# Sense.net
KiCad netlist of a schematic drawn in Altium Designer
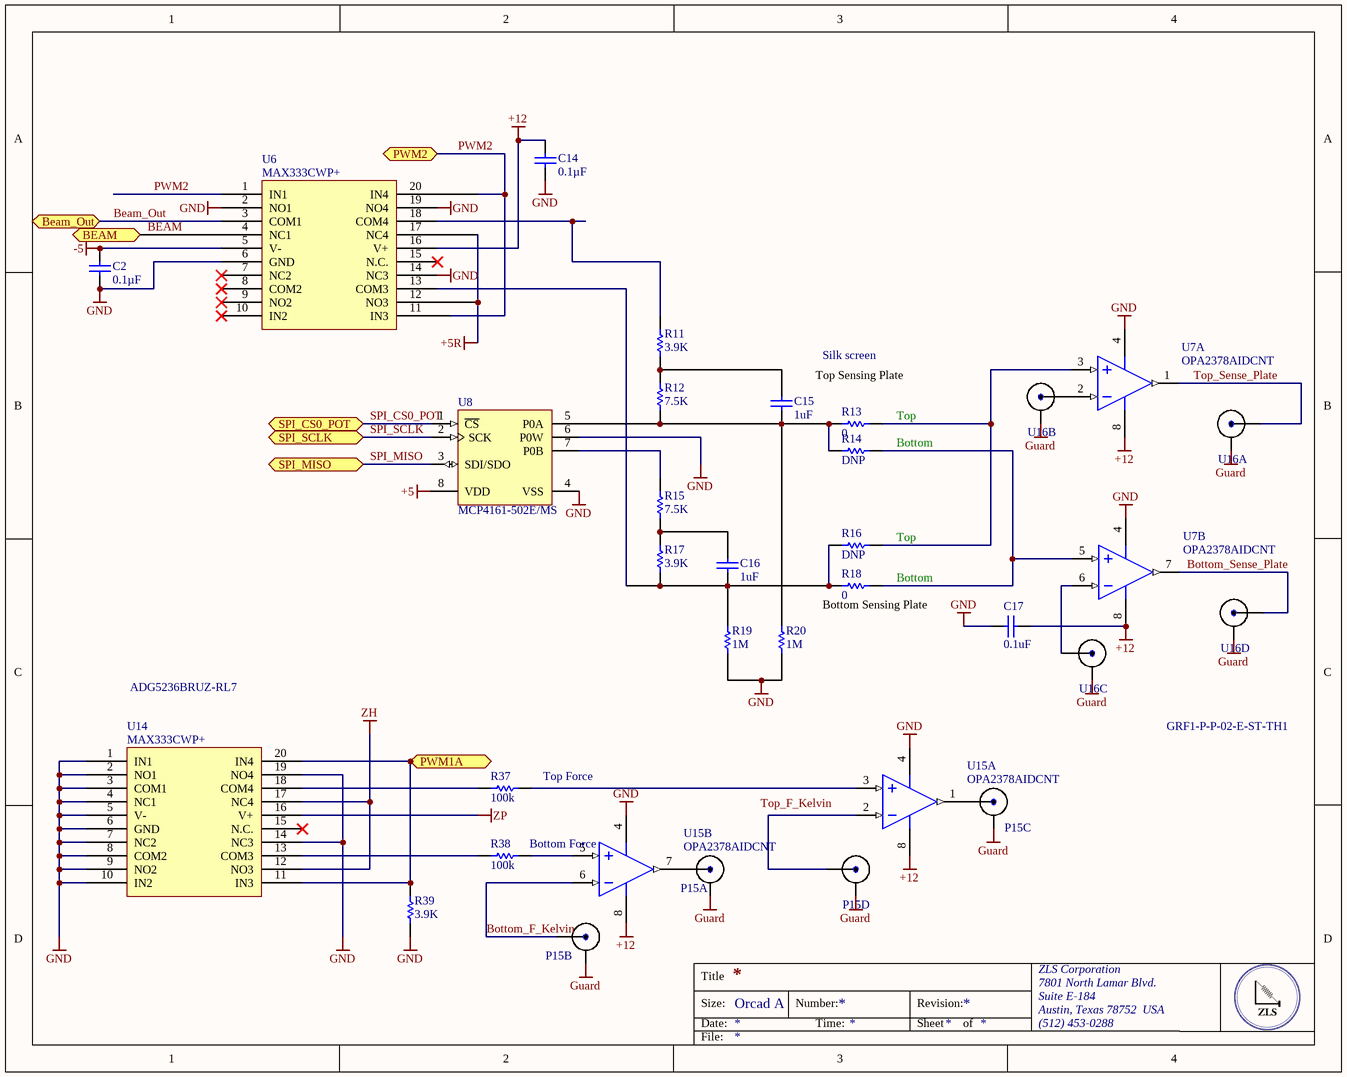
[diagram p0: Sense.SchDoc]

(export (version "E")
  (design (tool "Eeschema 10.0.6"))
  (components
    (comp (ref "C2")
      (value "CAP CER 0.1UF 25V X7R 0805")
      (footprint "CAPC0805(2012)145_N")
      (fields
        (field (name "MANUFACTURER") "Murata Electronics North America")
        (field (name "MANUFACTURER PART NUMBER") "GRM21BR71E104KA01L")
        (field (name "CAPACITANCE") "0.1µF")
        (field (name "TOLERANCE") "±10%")
      )
      (libsource (lib "Altium Content Vault") (part "CMP-1036-04795-1"))
    )
    (comp (ref "C14")
      (value "CAP CER 0.1UF 25V X7R 0805")
      (footprint "CAPC0805(2012)145_N")
      (fields
        (field (name "MANUFACTURER") "Murata Electronics North America")
        (field (name "MANUFACTURER PART NUMBER") "GRM21BR71E104KA01L")
        (field (name "CAPACITANCE") "0.1µF")
        (field (name "TOLERANCE") "±10%")
      )
      (libsource (lib "Altium Content Vault") (part "CMP-1036-04795-1"))
    )
    (comp (ref "C15")
      (value "1uF")
      (footprint "CAPC0603(1608)100_L")
      (description "CAP 4.3pF 25V ±0.5pF 0603 (1608 Metric) Thickness 1mm SMD")
      (fields
        (field (name "MANUFACTURER") "Samsung Electro-Mechanics")
        (field (name "MANUFACTURER PART NUMBER") "CL10B105KA8NNNC")
      )
      (libsource (lib "Altium Content Vault") (part "CMP-1035-00303-1"))
    )
    (comp (ref "C16")
      (value "1uF")
      (footprint "CAPC0603(1608)100_L")
      (description "CAP 4.3pF 25V ±0.5pF 0603 (1608 Metric) Thickness 1mm SMD")
      (fields
        (field (name "MANUFACTURER") "Samsung Electro-Mechanics")
        (field (name "MANUFACTURER PART NUMBER") "CL10B105KA8NNNC")
      )
      (libsource (lib "Altium Content Vault") (part "CMP-1035-00303-1"))
    )
    (comp (ref "C17")
      (value "0.1uF")
      (footprint "CAPC0402(1005)60_L")
      (description "CAP CER 0.1UF 10V X7R 0402")
      (fields
        (field (name "MANUFACTURER") "Murata Electronics North America")
        (field (name "MANUFACTURER PART NUMBER") "GRM155R71A104KA01D")
      )
      (libsource (lib "Altium Content Vault") (part "CMP-1034-00252-1"))
    )
    (comp (ref "P15")
      (value "GRF1-P-P-04-E-ST-TH1")
      (footprint "GRF1-P-P-04-E-ST-TH1")
      (libsource (lib "ZLS_Schematic_lib") (part "GRF1-P-P-04-E-ST-TH1"))
    )
    (comp (ref "R11")
      (value "3.9K")
      (footprint "RESC0402(1005)_M")
      (libsource (lib "Altium Content Vault") (part "CMP-1011-00463-1"))
    )
    (comp (ref "R12")
      (value "7.5K")
      (footprint "RESC0402(1005)_M")
      (libsource (lib "Altium Content Vault") (part "CMP-1011-00463-1"))
    )
    (comp (ref "R13")
      (value "0")
      (footprint "RESC0402(1005)_M")
      (libsource (lib "Altium Content Vault") (part "CMP-1011-00651-1"))
    )
    (comp (ref "R14")
      (value "DNP")
      (footprint "RESC0402(1005)_M")
      (libsource (lib "Altium Content Vault") (part "CMP-1011-00651-1"))
    )
    (comp (ref "R15")
      (value "7.5K")
      (footprint "RESC0402(1005)_M")
      (libsource (lib "Altium Content Vault") (part "CMP-1011-00463-1"))
    )
    (comp (ref "R16")
      (value "DNP")
      (footprint "RESC0402(1005)_M")
      (libsource (lib "Altium Content Vault") (part "CMP-1011-00651-1"))
    )
    (comp (ref "R17")
      (value "3.9K")
      (footprint "RESC0402(1005)_M")
      (libsource (lib "Altium Content Vault") (part "CMP-1011-00463-1"))
    )
    (comp (ref "R18")
      (value "0")
      (footprint "RESC0402(1005)_M")
      (libsource (lib "Altium Content Vault") (part "CMP-1011-00651-1"))
    )
    (comp (ref "R19")
      (value "1M")
      (footprint "RESC0402(1005)_M")
      (libsource (lib "Altium Content Vault") (part "CMP-1011-00463-1"))
    )
    (comp (ref "R20")
      (value "1M")
      (footprint "RESC0402(1005)_M")
      (libsource (lib "Altium Content Vault") (part "CMP-1011-00463-1"))
    )
    (comp (ref "R37")
      (value "100k")
      (footprint "RESC0402(1005)_M")
      (libsource (lib "Altium Content Vault") (part "CMP-1011-00651-1"))
    )
    (comp (ref "R38")
      (value "100k")
      (footprint "RESC0402(1005)_M")
      (libsource (lib "Altium Content Vault") (part "CMP-1011-00651-1"))
    )
    (comp (ref "R39")
      (value "3.9K")
      (footprint "RESC0402(1005)_M")
      (libsource (lib "Altium Content Vault") (part "CMP-1011-00463-1"))
    )
    (comp (ref "U6")
      (value "MAX333CWP+")
      (footprint "TSOP65P640X90-20N")
      (description "IC SWITCH QUAD SPDT 20TSSOP")
      (fields (field (name "MANUFACTURER") "Maxim") (field (name "MANUFACTURER PART NUMBER") "MAX333AEUP+"))
      (libsource (lib "ZLS_Schematic_lib") (part "MAX333CWP+"))
    )
    (comp (ref "U7")
      (value "OPA2378AIDCNT")
      (footprint "DCN0008A_M")
      (fields (field (name "MANUFACTURER") "Texas Instruments"))
      (libsource (lib "Altium Content Vault") (part "CMP-0272-01124-3"))
    )
    (comp (ref "U8")
      (value "MCP4161-502E/MS")
      (footprint "MSOP-MS8_N")
      (description "7/8-Bit Single/Dual SPI Digital POT with Non-Volatile Memory, 8-Pin MSOP, Extended Temperature")
      (libsource (lib "Altium Content Vault") (part "CMP-0188-00907-2"))
    )
    (comp (ref "U14")
      (value "MAX333CWP+")
      (footprint "TSOP65P640X90-20N")
      (description "IC SWITCH QUAD SPDT 20TSSOP")
      (fields (field (name "MANUFACTURER") "Maxim") (field (name "MANUFACTURER PART NUMBER") "MAX333AEUP+"))
      (libsource (lib "ZLS_Schematic_lib") (part "MAX333CWP+"))
    )
    (comp (ref "U15")
      (value "OPA2378AIDCNT")
      (footprint "DCN0008A_M")
      (fields (field (name "MANUFACTURER") "Texas Instruments"))
      (libsource (lib "Altium Content Vault") (part "CMP-0272-01124-3"))
    )
    (comp (ref "U16")
      (value "GRF1-P-P-04-E-ST-TH1")
      (footprint "GRF1-P-P-04-E-ST-TH1")
      (libsource (lib "ZLS_Schematic_lib") (part "GRF1-P-P-04-E-ST-TH1"))
    )
  )
  (nets
    (net (code "1") (name "+5") (class "Default")
      (node (ref "U8") (pin "8") (pinfunction "VDD_8") (pintype "power_in"))
    )
    (net (code "2") (name "+5R") (class "Default")
      (node (ref "U6") (pin "12") (pinfunction "NO3_12") (pintype "passive"))
      (node (ref "U6") (pin "17") (pinfunction "NC4_17") (pintype "passive"))
    )
    (net (code "3") (name "+12") (class "Default")
      (node (ref "C14") (pin "2") (pinfunction "2_2") (pintype "passive"))
      (node (ref "C17") (pin "2") (pinfunction "2_2") (pintype "passive"))
      (node (ref "U15") (pin "8") (pinfunction "V+_8") (pintype "power_in"))
      (node (ref "U6") (pin "16") (pinfunction "V+_16") (pintype "power_in"))
      (node (ref "U7") (pin "8") (pinfunction "V+_8") (pintype "power_in"))
    )
    (net (code "4") (name "-5") (class "Default")
      (node (ref "C2") (pin "1") (pinfunction "1_1") (pintype "passive"))
      (node (ref "U6") (pin "5") (pinfunction "V-_5") (pintype "power_in"))
    )
    (net (code "5") (name "/BEAM") (class "Default")
      (node (ref "U6") (pin "4") (pinfunction "NC1_4") (pintype "passive"))
    )
    (net (code "6") (name "/Beam_Out") (class "Default")
      (node (ref "U6") (pin "3") (pinfunction "COM1_3") (pintype "passive"))
    )
    (net (code "7") (name "/Bottom_F_Kelvin") (class "Default")
      (node (ref "P15") (pin "2") (pinfunction "2_2") (pintype "passive"))
      (node (ref "U15") (pin "6") (pinfunction "IN_B-_6") (pintype "input"))
    )
    (net (code "8") (name "/Bottom_Sense_Plate") (class "Default")
      (node (ref "U16") (pin "4") (pinfunction "4_4") (pintype "passive"))
      (node (ref "U7") (pin "7") (pinfunction "OUT_B_7") (pintype "output"))
    )
    (net (code "9") (name "/PWM1A") (class "Default")
      (node (ref "R39") (pin "2") (pinfunction "2_2") (pintype "passive"))
      (node (ref "U14") (pin "11") (pinfunction "IN3_11") (pintype "passive"))
      (node (ref "U14") (pin "20") (pinfunction "IN4_20") (pintype "passive"))
    )
    (net (code "10") (name "/PWM2") (class "Default")
      (node (ref "U6") (pin "1") (pinfunction "IN1_1") (pintype "passive"))
      (node (ref "U6") (pin "11") (pinfunction "IN3_11") (pintype "passive"))
      (node (ref "U6") (pin "20") (pinfunction "IN4_20") (pintype "passive"))
    )
    (net (code "11") (name "/SPI_CS0_POT") (class "Default")
      (node (ref "U8") (pin "1") (pinfunction "~{CS}_1") (pintype "input"))
    )
    (net (code "12") (name "/SPI_MISO") (class "Default")
      (node (ref "U8") (pin "3") (pinfunction "SDI/SDO_3") (pintype "bidirectional"))
    )
    (net (code "13") (name "/SPI_SCLK") (class "Default")
      (node (ref "U8") (pin "2") (pinfunction "SCK_2") (pintype "input"))
    )
    (net (code "15") (name "/Top_Sense_Plate") (class "Default")
      (node (ref "U16") (pin "1") (pinfunction "1_1") (pintype "passive"))
      (node (ref "U7") (pin "1") (pinfunction "OUT_A_1") (pintype "output"))
    )
    (net (code "16") (name "GND") (class "Default")
      (node (ref "C14") (pin "1") (pinfunction "1_1") (pintype "passive"))
      (node (ref "C17") (pin "1") (pinfunction "1_1") (pintype "passive"))
      (node (ref "C2") (pin "2") (pinfunction "2_2") (pintype "passive"))
      (node (ref "R19") (pin "1") (pinfunction "1_1") (pintype "passive"))
      (node (ref "R20") (pin "1") (pinfunction "1_1") (pintype "passive"))
      (node (ref "R39") (pin "1") (pinfunction "1_1") (pintype "passive"))
      (node (ref "U14") (pin "1") (pinfunction "IN1_1") (pintype "passive"))
      (node (ref "U14") (pin "10") (pinfunction "IN2_10") (pintype "passive"))
      (node (ref "U14") (pin "14") (pinfunction "NC3_14") (pintype "passive"))
      (node (ref "U14") (pin "19") (pinfunction "NO4_19") (pintype "passive"))
      (node (ref "U14") (pin "2") (pinfunction "NO1_2") (pintype "passive"))
      (node (ref "U14") (pin "3") (pinfunction "COM1_3") (pintype "passive"))
      (node (ref "U14") (pin "4") (pinfunction "NC1_4") (pintype "passive"))
      (node (ref "U14") (pin "5") (pinfunction "V-_5") (pintype "power_in"))
      (node (ref "U14") (pin "6") (pinfunction "GND_6") (pintype "passive"))
      (node (ref "U14") (pin "7") (pinfunction "NC2_7") (pintype "passive"))
      (node (ref "U14") (pin "8") (pinfunction "COM2_8") (pintype "passive"))
      (node (ref "U14") (pin "9") (pinfunction "NO2_9") (pintype "passive"))
      (node (ref "U15") (pin "4") (pinfunction "V-_4") (pintype "power_in"))
      (node (ref "U6") (pin "14") (pinfunction "NC3_14") (pintype "passive"))
      (node (ref "U6") (pin "19") (pinfunction "NO4_19") (pintype "passive"))
      (node (ref "U6") (pin "2") (pinfunction "NO1_2") (pintype "passive"))
      (node (ref "U6") (pin "6") (pinfunction "GND_6") (pintype "passive"))
      (node (ref "U7") (pin "4") (pinfunction "V-_4") (pintype "power_in"))
      (node (ref "U8") (pin "4") (pinfunction "VSS_4") (pintype "power_in"))
      (node (ref "U8") (pin "6") (pinfunction "P0W_6") (pintype "passive"))
    )
    (net (code "17") (name "Guard") (class "Default")
      (node (ref "P15") (pin "5") (pinfunction "5_5") (pintype "passive"))
      (node (ref "P15") (pin "6") (pinfunction "6_6") (pintype "passive"))
      (node (ref "P15") (pin "7") (pinfunction "7_7") (pintype "passive"))
      (node (ref "P15") (pin "8") (pinfunction "8_8") (pintype "passive"))
      (node (ref "U16") (pin "5") (pinfunction "5_5") (pintype "passive"))
      (node (ref "U16") (pin "6") (pinfunction "6_6") (pintype "passive"))
      (node (ref "U16") (pin "7") (pinfunction "7_7") (pintype "passive"))
      (node (ref "U16") (pin "8") (pinfunction "8_8") (pintype "passive"))
    )
    (net (code "18") (name "Net-(C15-Pad2)") (class "Default")
      (node (ref "C15") (pin "2") (pinfunction "2_2") (pintype "passive"))
      (node (ref "R11") (pin "1") (pinfunction "1_1") (pintype "passive"))
      (node (ref "R12") (pin "2") (pinfunction "2_2") (pintype "passive"))
    )
    (net (code "19") (name "Net-(C16-Pad2)") (class "Default")
      (node (ref "C16") (pin "2") (pinfunction "2_2") (pintype "passive"))
      (node (ref "R15") (pin "1") (pinfunction "1_1") (pintype "passive"))
      (node (ref "R17") (pin "2") (pinfunction "2_2") (pintype "passive"))
    )
    (net (code "20") (name "Net-(U6-COM3)") (class "Default")
      (node (ref "C16") (pin "1") (pinfunction "1_1") (pintype "passive"))
      (node (ref "R16") (pin "2") (pinfunction "2_2") (pintype "passive"))
      (node (ref "R17") (pin "1") (pinfunction "1_1") (pintype "passive"))
      (node (ref "R18") (pin "2") (pinfunction "2_2") (pintype "passive"))
      (node (ref "R19") (pin "2") (pinfunction "2_2") (pintype "passive"))
      (node (ref "U6") (pin "13") (pinfunction "COM3_13") (pintype "passive"))
    )
    (net (code "21") (name "Net-(U6-COM4)") (class "Default")
      (node (ref "R11") (pin "2") (pinfunction "2_2") (pintype "passive"))
      (node (ref "U6") (pin "18") (pinfunction "COM4_18") (pintype "passive"))
    )
    (net (code "22") (name "Net-(U7A-IN_A+)") (class "Default")
      (node (ref "R13") (pin "1") (pinfunction "1_1") (pintype "passive"))
      (node (ref "R16") (pin "1") (pinfunction "1_1") (pintype "passive"))
      (node (ref "U7") (pin "3") (pinfunction "IN_A+_3") (pintype "input"))
    )
    (net (code "23") (name "Net-(U7A-IN_A-)") (class "Default")
      (node (ref "U16") (pin "2") (pinfunction "2_2") (pintype "passive"))
      (node (ref "U7") (pin "2") (pinfunction "IN_A-_2") (pintype "input"))
    )
    (net (code "24") (name "Net-(U7B-IN_B+)") (class "Default")
      (node (ref "R14") (pin "1") (pinfunction "1_1") (pintype "passive"))
      (node (ref "R18") (pin "1") (pinfunction "1_1") (pintype "passive"))
      (node (ref "U7") (pin "5") (pinfunction "IN_B+_5") (pintype "input"))
    )
    (net (code "25") (name "Net-(U7B-IN_B-)") (class "Default")
      (node (ref "U16") (pin "3") (pinfunction "3_3") (pintype "passive"))
      (node (ref "U7") (pin "6") (pinfunction "IN_B-_6") (pintype "input"))
    )
    (net (code "26") (name "Net-(U8-P0A)") (class "Default")
      (node (ref "C15") (pin "1") (pinfunction "1_1") (pintype "passive"))
      (node (ref "R12") (pin "1") (pinfunction "1_1") (pintype "passive"))
      (node (ref "R13") (pin "2") (pinfunction "2_2") (pintype "passive"))
      (node (ref "R14") (pin "2") (pinfunction "2_2") (pintype "passive"))
      (node (ref "R20") (pin "2") (pinfunction "2_2") (pintype "passive"))
      (node (ref "U8") (pin "5") (pinfunction "P0A_5") (pintype "passive"))
    )
    (net (code "27") (name "Net-(U8-P0B)") (class "Default")
      (node (ref "R15") (pin "2") (pinfunction "2_2") (pintype "passive"))
      (node (ref "U8") (pin "7") (pinfunction "P0B_7") (pintype "passive"))
    )
    (net (code "28") (name "Net-(U14-COM3)") (class "Default")
      (node (ref "R38") (pin "2") (pinfunction "2_2") (pintype "passive"))
      (node (ref "U14") (pin "13") (pinfunction "COM3_13") (pintype "passive"))
    )
    (net (code "29") (name "Net-(U14-COM4)") (class "Default")
      (node (ref "R37") (pin "2") (pinfunction "2_2") (pintype "passive"))
      (node (ref "U14") (pin "18") (pinfunction "COM4_18") (pintype "passive"))
    )
    (net (code "30") (name "Net-(U15A-IN_A+)") (class "Default")
      (node (ref "R37") (pin "1") (pinfunction "1_1") (pintype "passive"))
      (node (ref "U15") (pin "3") (pinfunction "IN_A+_3") (pintype "input"))
    )
    (net (code "31") (name "Net-(U15A-IN_A-)") (class "Default")
      (node (ref "P15") (pin "4") (pinfunction "4_4") (pintype "passive"))
      (node (ref "U15") (pin "2") (pinfunction "IN_A-_2") (pintype "input"))
    )
    (net (code "32") (name "Net-(U15A-OUT_A)") (class "Default")
      (node (ref "P15") (pin "3") (pinfunction "3_3") (pintype "passive"))
      (node (ref "U15") (pin "1") (pinfunction "OUT_A_1") (pintype "output"))
    )
    (net (code "33") (name "Net-(U15B-IN_B+)") (class "Default")
      (node (ref "R38") (pin "1") (pinfunction "1_1") (pintype "passive"))
      (node (ref "U15") (pin "5") (pinfunction "IN_B+_5") (pintype "input"))
    )
    (net (code "34") (name "Net-(U15B-OUT_B)") (class "Default")
      (node (ref "P15") (pin "1") (pinfunction "1_1") (pintype "passive"))
      (node (ref "U15") (pin "7") (pinfunction "OUT_B_7") (pintype "output"))
    )
    (net (code "35") (name "ZH") (class "Default")
      (node (ref "U14") (pin "12") (pinfunction "NO3_12") (pintype "passive"))
      (node (ref "U14") (pin "17") (pinfunction "NC4_17") (pintype "passive"))
    )
    (net (code "36") (name "ZP") (class "Default")
      (node (ref "U14") (pin "16") (pinfunction "V+_16") (pintype "power_in"))
    )
    (net (code "37") (name "unconnected-(U6-COM2-Pad8)") (class "Default")
      (node (ref "U6") (pin "8") (pinfunction "COM2_8") (pintype "passive+no_connect"))
    )
    (net (code "38") (name "unconnected-(U6-IN2-Pad10)") (class "Default")
      (node (ref "U6") (pin "10") (pinfunction "IN2_10") (pintype "passive+no_connect"))
    )
    (net (code "39") (name "unconnected-(U6-N.C.-Pad15)") (class "Default")
      (node (ref "U6") (pin "15") (pinfunction "N.C._15") (pintype "passive+no_connect"))
    )
    (net (code "40") (name "unconnected-(U6-NC2-Pad7)") (class "Default")
      (node (ref "U6") (pin "7") (pinfunction "NC2_7") (pintype "passive+no_connect"))
    )
    (net (code "41") (name "unconnected-(U6-NO2-Pad9)") (class "Default")
      (node (ref "U6") (pin "9") (pinfunction "NO2_9") (pintype "passive+no_connect"))
    )
    (net (code "42") (name "unconnected-(U14-N.C.-Pad15)") (class "Default")
      (node (ref "U14") (pin "15") (pinfunction "N.C._15") (pintype "passive+no_connect"))
    )
  )
)
